# Dimmer.net
KiCad netlist of a schematic drawn in Altium Designer
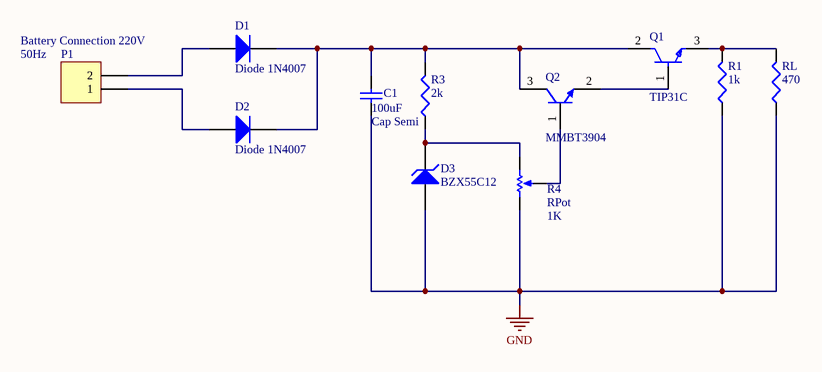
[diagram p0: Dimmer.SchDoc]

(export (version "E")
  (design (tool "Eeschema 10.0.6"))
  (components
    (comp (ref "C1")
      (value "Cap Semi")
      (footprint "C1206")
      (description "Capacitor (Semiconductor SIM Model)")
      (fields (field (name "ALTIUM_VALUE") "100uF") (field (name "PUBLISHER") "Altium Limited"))
      (libsource (lib "Miscellaneous Devices") (part "Cap Semi"))
    )
    (comp (ref "D1")
      (value "Diode 1N4007")
      (footprint "DO-41")
      (description "1 Amp General Purpose Rectifier")
      (fields (field (name "PUBLISHER") "Altium Limited"))
      (libsource (lib "Miscellaneous Devices") (part "Diode 1N4007"))
    )
    (comp (ref "D2")
      (value "Diode 1N4007")
      (footprint "DO-41")
      (description "1 Amp General Purpose Rectifier")
      (fields (field (name "PUBLISHER") "Altium Limited"))
      (libsource (lib "Miscellaneous Devices") (part "Diode 1N4007"))
    )
    (comp (ref "D3")
      (value "BZX55C12")
      (footprint "DO-35")
      (description "Silicon Epitaxial Planar Zener Diode (0.3 to 0.5W)")
      (fields (field (name "PUBLISHER") "Altium Limited"))
      (libsource (lib "altium-import") (part "root_1_BZX55C12_"))
    )
    (comp (ref "P1")
      (value "Battery Connection 220V")
      (footprint "HDR1X2H")
      (description "Header, 2-Pin, Right Angle")
      (fields
        (field (name "VOLTAGE") "220V")
        (field (name "FREQUENCY") "50Hz")
        (field (name "PUBLISHER") "Altium Limited")
      )
      (libsource (lib "Miscellaneous Connectors") (part "Header 2H"))
    )
    (comp (ref "Q1")
      (value "TIP31C")
      (footprint "FP-TO-220-P0A0015988-MFG")
      (description "TRANS NPN 100V 3A TO-220")
      (fields
        (field (name "OCTOPART") "https://octopart.com/tip31c-stmicroelectronics-15555")
        (field (name "MANUFACTURER") "STMicroelectronics")
      )
      (libsource (lib "Altium Content Vault") (part "1c57d9dae74fe2702546667b0e849db"))
    )
    (comp (ref "Q2")
      (value "MMBT3904")
      (footprint "FAIR-SOT23-3_V")
      (description "NPN General Purpose Amplifier, 40 V, 0.2 A, -55 to 150 degC, 3-Pin SOT23, RoHS, Tape and Reel")
      (fields (field (name "TOLERANCE") "30ppm"))
      (libsource (lib "Altium Content Vault") (part "BJT-NPN-BEC-3"))
    )
    (comp (ref "R1")
      (value "1k")
      (footprint "J1-0603")
      (description "Resistor")
      (fields (field (name "Comment") "Res3") (field (name "PUBLISHER") "Altium Limited"))
      (libsource (lib "Miscellaneous Devices") (part "Res3"))
    )
    (comp (ref "R3")
      (value "2k")
      (footprint "J1-0603")
      (description "Resistor")
      (fields (field (name "Comment") "Res3") (field (name "PUBLISHER") "Altium Limited"))
      (libsource (lib "Miscellaneous Devices") (part "Res3"))
    )
    (comp (ref "R4")
      (value "RPot")
      (footprint "VR5")
      (description "Potentiometer")
      (fields (field (name "ALTIUM_VALUE") "1K") (field (name "PUBLISHER") "Altium Limited"))
      (libsource (lib "Miscellaneous Devices") (part "RPot"))
    )
    (comp (ref "RL")
      (value "470")
      (footprint "J1-0603")
      (description "Resistor")
      (fields (field (name "Comment") "Res3") (field (name "PUBLISHER") "Altium Limited"))
      (libsource (lib "Miscellaneous Devices") (part "Res3"))
    )
  )
  (nets
    (net (code "1") (name "GND") (class "Default")
      (node (ref "C1") (pin "1") (pinfunction "1_1") (pintype "passive"))
      (node (ref "D3") (pin "1") (pinfunction "A_1") (pintype "passive"))
      (node (ref "R1") (pin "1") (pinfunction "1_1") (pintype "passive"))
      (node (ref "R4") (pin "1") (pinfunction "TOP_1") (pintype "passive"))
      (node (ref "RL") (pin "1") (pinfunction "1_1") (pintype "passive"))
    )
    (net (code "2") (name "Net-(D1-A)") (class "Default")
      (node (ref "D1") (pin "1") (pinfunction "A_1") (pintype "passive"))
      (node (ref "P1") (pin "2") (pinfunction "2_2") (pintype "passive"))
    )
    (net (code "3") (name "Net-(D1-K)") (class "Default")
      (node (ref "C1") (pin "2") (pinfunction "2_2") (pintype "passive"))
      (node (ref "D1") (pin "2") (pinfunction "K_2") (pintype "passive"))
      (node (ref "D2") (pin "2") (pinfunction "K_2") (pintype "passive"))
      (node (ref "Q1") (pin "2") (pinfunction "C_2") (pintype "passive"))
      (node (ref "Q2") (pin "3") (pinfunction "C_3") (pintype "passive"))
      (node (ref "R3") (pin "2") (pinfunction "2_2") (pintype "passive"))
    )
    (net (code "4") (name "Net-(D2-A)") (class "Default")
      (node (ref "D2") (pin "1") (pinfunction "A_1") (pintype "passive"))
      (node (ref "P1") (pin "1") (pinfunction "1_1") (pintype "passive"))
    )
    (net (code "5") (name "Net-(D3-K)") (class "Default")
      (node (ref "D3") (pin "2") (pinfunction "K_2") (pintype "passive"))
      (node (ref "R3") (pin "1") (pinfunction "1_1") (pintype "passive"))
      (node (ref "R4") (pin "2") (pinfunction "BOT_2") (pintype "passive"))
    )
    (net (code "6") (name "Net-(Q1-B)") (class "Default")
      (node (ref "Q1") (pin "1") (pinfunction "B_1") (pintype "passive"))
      (node (ref "Q2") (pin "2") (pinfunction "E_2") (pintype "passive"))
    )
    (net (code "7") (name "Net-(Q1-E)") (class "Default")
      (node (ref "Q1") (pin "3") (pinfunction "E_3") (pintype "passive"))
      (node (ref "R1") (pin "2") (pinfunction "2_2") (pintype "passive"))
      (node (ref "RL") (pin "2") (pinfunction "2_2") (pintype "passive"))
    )
    (net (code "8") (name "Net-(Q2-B)") (class "Default")
      (node (ref "Q2") (pin "1") (pinfunction "B_1") (pintype "passive"))
      (node (ref "R4") (pin "3") (pinfunction "TAP_3") (pintype "passive"))
    )
  )
)
